# brick_i2c_lsm9ds1.net
KiCad netlist of a schematic drawn in EAGLE
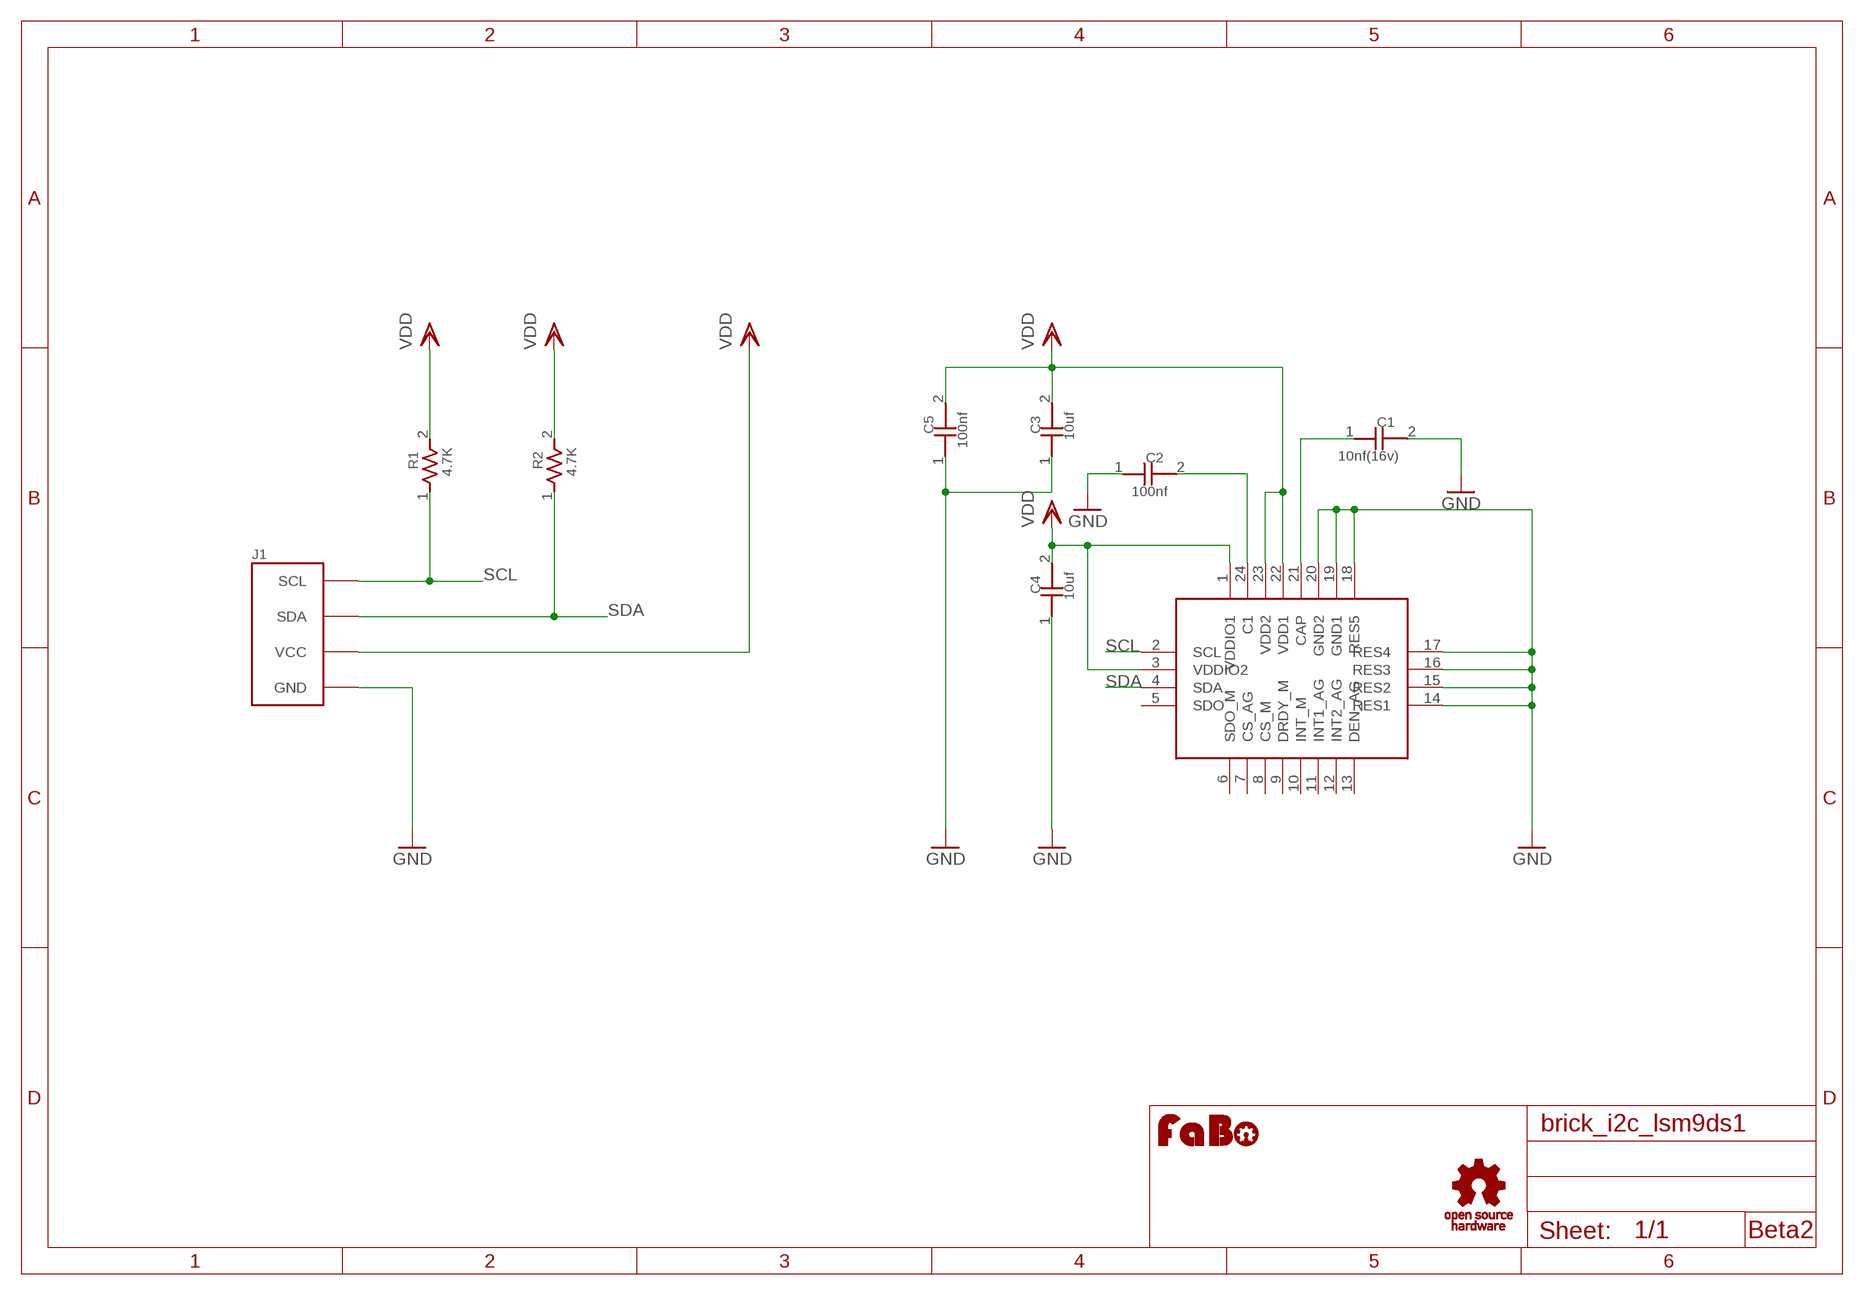
[diagram p0: schematic, sheet 1]

(export (version "E")
  (design (tool "Eeschema 10.0.6"))
  (components
    (comp (ref "C1")
      (value "10nf(16v)")
      (footprint "eagle-import:0603")
      (libsource (lib "eagle-import") (part "CAPACITOR0603"))
    )
    (comp (ref "C2")
      (value "100nf")
      (footprint "eagle-import:0603")
      (libsource (lib "eagle-import") (part "CAPACITOR0603"))
    )
    (comp (ref "C3")
      (value "10uf")
      (footprint "eagle-import:0603")
      (libsource (lib "eagle-import") (part "CAPACITOR0603"))
    )
    (comp (ref "C4")
      (value "10uf")
      (footprint "eagle-import:0603")
      (libsource (lib "eagle-import") (part "CAPACITOR0603"))
    )
    (comp (ref "C5")
      (value "100nf")
      (footprint "eagle-import:0603")
      (libsource (lib "eagle-import") (part "CAPACITOR0603"))
    )
    (comp (ref "J1")
      (value "BRICK_I2C")
      (footprint "eagle-import:BRICK_I2C")
      (libsource (lib "eagle-import") (part "BRICK_I2C"))
    )
    (comp (ref "R1")
      (value "4.7K")
      (footprint "eagle-import:0603")
      (libsource (lib "eagle-import") (part "RESISTOR0603"))
    )
    (comp (ref "R2")
      (value "4.7K")
      (footprint "eagle-import:0603")
      (libsource (lib "eagle-import") (part "RESISTOR0603"))
    )
    (comp (ref "U$1")
      (value "ST-LSM9DS1TR")
      (footprint "eagle-import:ST-LSM9DS1TR")
      (libsource (lib "eagle-import") (part "ST-LSM9DS1TR"))
    )
    (comp (ref "U$3")
      (value "LOGO_OSHW_T-M")
      (footprint "eagle-import:LOGO_OSHW_T_M")
      (libsource (lib "eagle-import") (part "LOGO_OSHW_T-M"))
    )
    (comp (ref "U$4")
      (value "LOGO_FABO-M")
      (footprint "eagle-import:LOGO_FABO_M")
      (libsource (lib "eagle-import") (part "LOGO_FABO-M"))
    )
  )
  (nets
    (net (code "1") (name "/SCL") (class "Default")
      (node (ref "J1") (pin "SCL") (pinfunction "SCL_SCL") (pintype "bidirectional"))
      (node (ref "R1") (pin "1") (pinfunction "1_1") (pintype "passive"))
      (node (ref "U$1") (pin "2") (pinfunction "SCL_2") (pintype "bidirectional"))
    )
    (net (code "2") (name "/SDA") (class "Default")
      (node (ref "J1") (pin "SDA") (pinfunction "SDA_SDA") (pintype "bidirectional"))
      (node (ref "R2") (pin "1") (pinfunction "1_1") (pintype "passive"))
      (node (ref "U$1") (pin "4") (pinfunction "SDA_4") (pintype "bidirectional"))
    )
    (net (code "3") (name "GND") (class "Default")
      (node (ref "C1") (pin "2") (pinfunction "2_2") (pintype "passive"))
      (node (ref "C2") (pin "1") (pinfunction "1_1") (pintype "passive"))
      (node (ref "C3") (pin "1") (pinfunction "1_1") (pintype "passive"))
      (node (ref "C4") (pin "1") (pinfunction "1_1") (pintype "passive"))
      (node (ref "C5") (pin "1") (pinfunction "1_1") (pintype "passive"))
      (node (ref "J1") (pin "GND") (pinfunction "GND_GND") (pintype "bidirectional"))
      (node (ref "U$1") (pin "14") (pinfunction "RES1_14") (pintype "bidirectional"))
      (node (ref "U$1") (pin "15") (pinfunction "RES2_15") (pintype "bidirectional"))
      (node (ref "U$1") (pin "16") (pinfunction "RES3_16") (pintype "bidirectional"))
      (node (ref "U$1") (pin "17") (pinfunction "RES4_17") (pintype "bidirectional"))
      (node (ref "U$1") (pin "18") (pinfunction "RES5_18") (pintype "bidirectional"))
      (node (ref "U$1") (pin "19") (pinfunction "GND1_19") (pintype "bidirectional"))
      (node (ref "U$1") (pin "20") (pinfunction "GND2_20") (pintype "bidirectional"))
    )
    (net (code "4") (name "Net-(U$1-C1)") (class "Default")
      (node (ref "C2") (pin "2") (pinfunction "2_2") (pintype "passive"))
      (node (ref "U$1") (pin "24") (pinfunction "C1_24") (pintype "bidirectional"))
    )
    (net (code "5") (name "Net-(U$1-CAP)") (class "Default")
      (node (ref "C1") (pin "1") (pinfunction "1_1") (pintype "passive"))
      (node (ref "U$1") (pin "21") (pinfunction "CAP_21") (pintype "bidirectional"))
    )
    (net (code "6") (name "VDD") (class "Default")
      (node (ref "C3") (pin "2") (pinfunction "2_2") (pintype "passive"))
      (node (ref "C4") (pin "2") (pinfunction "2_2") (pintype "passive"))
      (node (ref "C5") (pin "2") (pinfunction "2_2") (pintype "passive"))
      (node (ref "J1") (pin "VCC") (pinfunction "VCC_VCC") (pintype "bidirectional"))
      (node (ref "R1") (pin "2") (pinfunction "2_2") (pintype "passive"))
      (node (ref "R2") (pin "2") (pinfunction "2_2") (pintype "passive"))
      (node (ref "U$1") (pin "1") (pinfunction "VDDIO1_1") (pintype "bidirectional"))
      (node (ref "U$1") (pin "22") (pinfunction "VDD1_22") (pintype "bidirectional"))
      (node (ref "U$1") (pin "23") (pinfunction "VDD2_23") (pintype "bidirectional"))
      (node (ref "U$1") (pin "3") (pinfunction "VDDIO2_3") (pintype "bidirectional"))
    )
    (net (code "7") (name "unconnected-(U$1-CS_AG-Pad7)") (class "Default")
      (node (ref "U$1") (pin "7") (pinfunction "CS_AG_7") (pintype "bidirectional"))
    )
    (net (code "8") (name "unconnected-(U$1-CS_M-Pad8)") (class "Default")
      (node (ref "U$1") (pin "8") (pinfunction "CS_M_8") (pintype "bidirectional"))
    )
    (net (code "9") (name "unconnected-(U$1-DEN_AG-Pad13)") (class "Default")
      (node (ref "U$1") (pin "13") (pinfunction "DEN_AG_13") (pintype "bidirectional"))
    )
    (net (code "10") (name "unconnected-(U$1-DRDY_M-Pad9)") (class "Default")
      (node (ref "U$1") (pin "9") (pinfunction "DRDY_M_9") (pintype "bidirectional"))
    )
    (net (code "11") (name "unconnected-(U$1-INT1_AG-Pad11)") (class "Default")
      (node (ref "U$1") (pin "11") (pinfunction "INT1_AG_11") (pintype "bidirectional"))
    )
    (net (code "12") (name "unconnected-(U$1-INT2_AG-Pad12)") (class "Default")
      (node (ref "U$1") (pin "12") (pinfunction "INT2_AG_12") (pintype "bidirectional"))
    )
    (net (code "13") (name "unconnected-(U$1-INT_M-Pad10)") (class "Default")
      (node (ref "U$1") (pin "10") (pinfunction "INT_M_10") (pintype "bidirectional"))
    )
    (net (code "14") (name "unconnected-(U$1-SDO-Pad5)") (class "Default")
      (node (ref "U$1") (pin "5") (pinfunction "SDO_5") (pintype "bidirectional"))
    )
    (net (code "15") (name "unconnected-(U$1-SDO_M-Pad6)") (class "Default")
      (node (ref "U$1") (pin "6") (pinfunction "SDO_M_6") (pintype "bidirectional"))
    )
  )
)
